# breakout.net
KiCad netlist of a schematic drawn in EAGLE
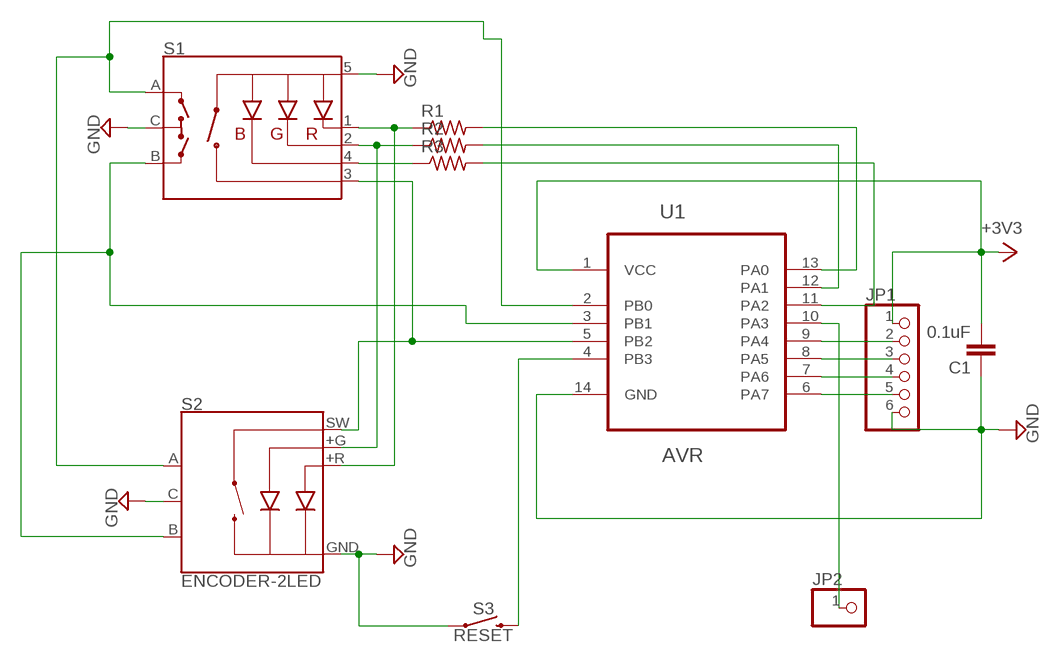
[diagram p0: schematic, sheet 1]

(export (version "E")
  (design (tool "Eeschema 10.0.6"))
  (components
    (comp (ref "C1")
      (value "0.1uF")
      (footprint "eagle-import:0603")
      (libsource (lib "eagle-import") (part "0.1UF-0603-25V-5%"))
    )
    (comp (ref "JP1")
      (value "PINHD-1X6")
      (footprint "eagle-import:1X06")
      (libsource (lib "eagle-import") (part "PINHD-1X6"))
    )
    (comp (ref "JP2")
      (value "PINHD-1X1")
      (footprint "eagle-import:1X01")
      (libsource (lib "eagle-import") (part "PINHD-1X1"))
    )
    (comp (ref "R1")
      (value "R-US_M1206")
      (footprint "eagle-import:M1206")
      (libsource (lib "eagle-import") (part "R-US_M1206"))
    )
    (comp (ref "R2")
      (value "R-US_M1206")
      (footprint "eagle-import:M1206")
      (libsource (lib "eagle-import") (part "R-US_M1206"))
    )
    (comp (ref "R3")
      (value "R-US_M1206")
      (footprint "eagle-import:M1206")
      (libsource (lib "eagle-import") (part "R-US_M1206"))
    )
    (comp (ref "S1")
      (value "ENCODER-RGB-SWITCH")
      (footprint "eagle-import:ENCODER_LED_3")
      (libsource (lib "eagle-import") (part "ENCODER-RGB-SWITCH"))
    )
    (comp (ref "S2")
      (value "ENCODER-2LED")
      (footprint "eagle-import:ENCODER_LED_2")
      (libsource (lib "eagle-import") (part "ENCODER-2LED"))
    )
    (comp (ref "S3")
      (value "RESET")
      (footprint "eagle-import:TACTILE_SWITCH_SMD_4.5MM")
      (libsource (lib "eagle-import") (part "MOMENTARY-SWITCH-SPST-SMD-4.5MM"))
    )
    (comp (ref "U1")
      (value "AVR")
      (footprint "eagle-import:SOIC127P600X175-14N")
      (fields (field (name "MPN") "ATTINY24-20SSU"))
      (libsource (lib "eagle-import") (part "ATTINY24-20SSU"))
    )
  )
  (nets
    (net (code "1") (name "+3V3") (class "Default")
      (node (ref "C1") (pin "2") (pinfunction "2_2") (pintype "passive"))
      (node (ref "JP1") (pin "1") (pinfunction "1_1") (pintype "passive"))
      (node (ref "U1") (pin "1") (pinfunction "VCC_1") (pintype "power_in"))
    )
    (net (code "2") (name "GND") (class "Default")
      (node (ref "C1") (pin "1") (pinfunction "1_1") (pintype "passive"))
      (node (ref "JP1") (pin "6") (pinfunction "6_6") (pintype "passive"))
      (node (ref "S1") (pin "5") (pinfunction "+_5") (pintype "passive"))
      (node (ref "S1") (pin "C") (pinfunction "C_C") (pintype "bidirectional"))
      (node (ref "S2") (pin "C") (pinfunction "C_C") (pintype "bidirectional"))
      (node (ref "S2") (pin "GND") (pinfunction "-_GND") (pintype "passive"))
      (node (ref "S3") (pin "2") (pinfunction "1_2") (pintype "passive"))
      (node (ref "S3") (pin "3") (pinfunction "1_3") (pintype "passive"))
      (node (ref "U1") (pin "14") (pinfunction "GND_14") (pintype "passive"))
    )
    (net (code "3") (name "Net-(S1--B)") (class "Default")
      (node (ref "R3") (pin "1") (pinfunction "1_1") (pintype "passive"))
      (node (ref "S1") (pin "4") (pinfunction "-B_4") (pintype "passive"))
    )
    (net (code "4") (name "Net-(S1--G)") (class "Default")
      (node (ref "R2") (pin "1") (pinfunction "1_1") (pintype "passive"))
      (node (ref "S1") (pin "2") (pinfunction "-G_2") (pintype "passive"))
      (node (ref "S2") (pin "+G") (pinfunction "+G_+G") (pintype "passive"))
    )
    (net (code "5") (name "Net-(S1--R)") (class "Default")
      (node (ref "R1") (pin "1") (pinfunction "1_1") (pintype "passive"))
      (node (ref "S1") (pin "1") (pinfunction "-R_1") (pintype "passive"))
      (node (ref "S2") (pin "+R") (pinfunction "+R_+R") (pintype "passive"))
    )
    (net (code "6") (name "Net-(S1-SW)") (class "Default")
      (node (ref "S1") (pin "3") (pinfunction "SW_3") (pintype "passive"))
      (node (ref "S2") (pin "SW") (pinfunction "SW_SW") (pintype "passive"))
      (node (ref "U1") (pin "5") (pinfunction "PB2_5") (pintype "bidirectional"))
    )
    (net (code "7") (name "Net-(U1-PA0)") (class "Default")
      (node (ref "R1") (pin "2") (pinfunction "2_2") (pintype "passive"))
      (node (ref "U1") (pin "13") (pinfunction "PA0_13") (pintype "bidirectional"))
    )
    (net (code "8") (name "Net-(U1-PA1)") (class "Default")
      (node (ref "R2") (pin "2") (pinfunction "2_2") (pintype "passive"))
      (node (ref "U1") (pin "12") (pinfunction "PA1_12") (pintype "bidirectional"))
    )
    (net (code "9") (name "Net-(U1-PA2)") (class "Default")
      (node (ref "R3") (pin "2") (pinfunction "2_2") (pintype "passive"))
      (node (ref "U1") (pin "11") (pinfunction "PA2_11") (pintype "bidirectional"))
    )
    (net (code "10") (name "Net-(U1-PA3)") (class "Default")
      (node (ref "JP2") (pin "1") (pinfunction "1_1") (pintype "passive"))
      (node (ref "U1") (pin "10") (pinfunction "PA3_10") (pintype "bidirectional"))
    )
    (net (code "11") (name "Net-(U1-PA4)") (class "Default")
      (node (ref "JP1") (pin "2") (pinfunction "2_2") (pintype "passive"))
      (node (ref "U1") (pin "9") (pinfunction "PA4_9") (pintype "bidirectional"))
    )
    (net (code "12") (name "Net-(U1-PA5)") (class "Default")
      (node (ref "JP1") (pin "3") (pinfunction "3_3") (pintype "passive"))
      (node (ref "U1") (pin "8") (pinfunction "PA5_8") (pintype "bidirectional"))
    )
    (net (code "13") (name "Net-(U1-PA6)") (class "Default")
      (node (ref "JP1") (pin "4") (pinfunction "4_4") (pintype "passive"))
      (node (ref "U1") (pin "7") (pinfunction "PA6_7") (pintype "bidirectional"))
    )
    (net (code "14") (name "Net-(U1-PA7)") (class "Default")
      (node (ref "JP1") (pin "5") (pinfunction "5_5") (pintype "passive"))
      (node (ref "U1") (pin "6") (pinfunction "PA7_6") (pintype "bidirectional"))
    )
    (net (code "15") (name "Net-(U1-PB0)") (class "Default")
      (node (ref "S1") (pin "A") (pinfunction "A_A") (pintype "bidirectional"))
      (node (ref "S2") (pin "A") (pinfunction "A_A") (pintype "bidirectional"))
      (node (ref "U1") (pin "2") (pinfunction "PB0_2") (pintype "bidirectional"))
    )
    (net (code "16") (name "Net-(U1-PB1)") (class "Default")
      (node (ref "S1") (pin "B") (pinfunction "B_B") (pintype "bidirectional"))
      (node (ref "S2") (pin "B") (pinfunction "B_B") (pintype "bidirectional"))
      (node (ref "U1") (pin "3") (pinfunction "PB1_3") (pintype "bidirectional"))
    )
    (net (code "17") (name "Net-(U1-PB3)") (class "Default")
      (node (ref "S3") (pin "1") (pinfunction "2_1") (pintype "passive"))
      (node (ref "S3") (pin "4") (pinfunction "2_4") (pintype "passive"))
      (node (ref "U1") (pin "4") (pinfunction "PB3_4") (pintype "bidirectional"))
    )
  )
)
